# Camera_IR.net
KiCad netlist of a schematic drawn in EasyEDA
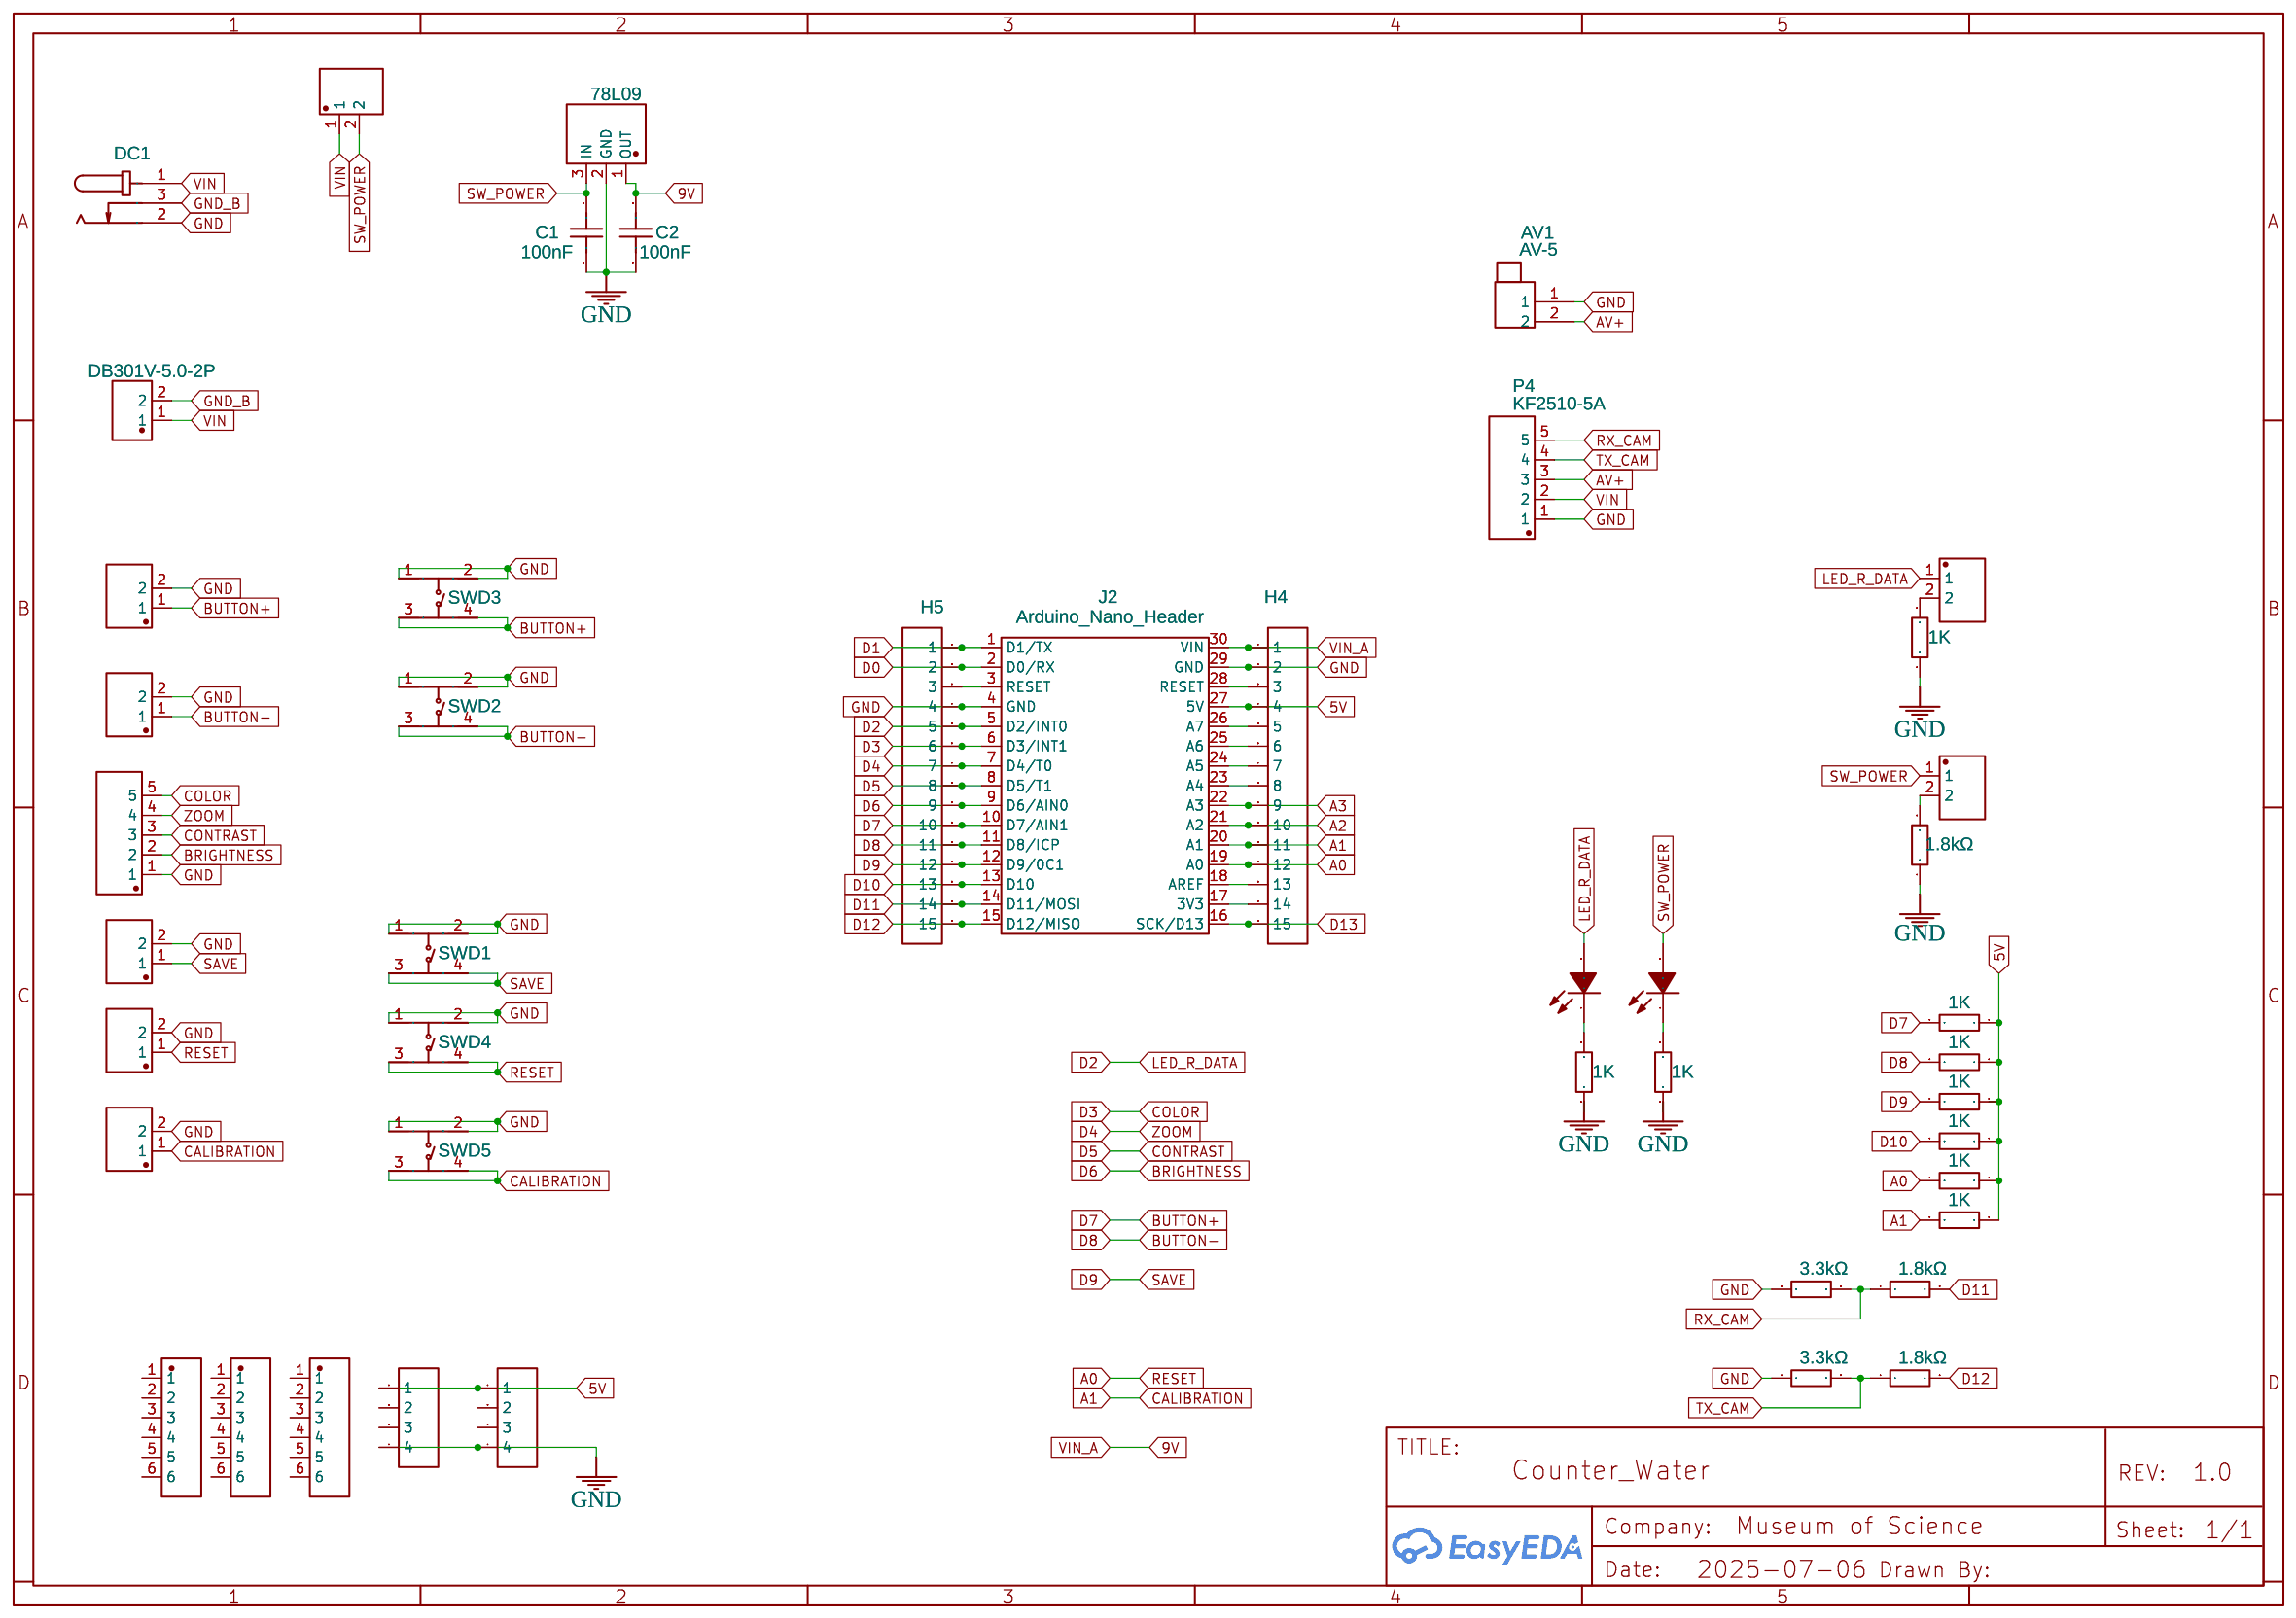
[diagram p0: schematic sheet]

(export (version "E")
  (design (tool "Eeschema 10.0.6"))
  (components
    (comp (ref "A0")
      (value "RESET")
      (fields (field (name "Manufacturer Part") "KF2510-2A") (field (name "Manufacturer") "BOOMELE"))
      (libsource (lib "") (part "KF2510-2A"))
    )
    (comp (ref "A1")
      (value "FFC")
      (fields (field (name "Manufacturer Part") "KF2510-2A") (field (name "Manufacturer") "BOOMELE"))
      (libsource (lib "") (part "KF2510-2A"))
    )
    (comp (ref "AV1")
      (value "AV-5")
      (fields (field (name "Manufacturer") "BOOMELE(博穆精密)"))
      (libsource (lib "") (part "AV-5"))
    )
    (comp (ref "C1")
      (value "100nF")
      (fields
        (field (name "Manufacturer Part") "CC0603KRX7R9BB104")
        (field (name "Manufacturer") "YAGEO(国巨)")
      )
      (libsource (lib "") (part "CC0603KRX7R9BB104"))
    )
    (comp (ref "C2")
      (value "100nF")
      (fields
        (field (name "Manufacturer Part") "CC0603KRX7R9BB104")
        (field (name "Manufacturer") "YAGEO(国巨)")
      )
      (libsource (lib "") (part "CC0603KRX7R9BB104"))
    )
    (comp (ref "D2")
      (value "LED")
      (fields (field (name "Manufacturer Part") "KF2510-2A") (field (name "Manufacturer") "BOOMELE"))
      (libsource (lib "") (part "KF2510-2A_3"))
    )
    (comp (ref "D7")
      (value "B+")
      (fields (field (name "Manufacturer Part") "KF2510-2A") (field (name "Manufacturer") "BOOMELE"))
      (libsource (lib "") (part "KF2510-2A_1"))
    )
    (comp (ref "D8")
      (value "B-")
      (fields (field (name "Manufacturer Part") "KF2510-2A") (field (name "Manufacturer") "BOOMELE"))
      (libsource (lib "") (part "KF2510-2A_1"))
    )
    (comp (ref "D9")
      (value "SAVE")
      (fields (field (name "Manufacturer Part") "KF2510-2A") (field (name "Manufacturer") "BOOMELE"))
      (libsource (lib "") (part "KF2510-2A_1"))
    )
    (comp (ref "DC1")
      (value "DC")
      (fields (field (name "Manufacturer Part") "DC005-2.0MM") (field (name "Manufacturer") "SOFNG"))
      (libsource (lib "") (part "DC005-2.0MM"))
    )
    (comp (ref "ERL1")
      (value "1K")
      (fields (field (name "Manufacturer Part") "0603WAF1001T5E") (field (name "Manufacturer") "UniOhm"))
      (libsource (lib "") (part "0603WAF1001T5E_1"))
    )
    (comp (ref "ERL2")
      (value "1K")
      (fields (field (name "Manufacturer Part") "0603WAF1001T5E") (field (name "Manufacturer") "UniOhm"))
      (libsource (lib "") (part "0603WAF1001T5E"))
    )
    (comp (ref "ERL3")
      (value "1K")
      (fields (field (name "Manufacturer Part") "0603WAF1001T5E") (field (name "Manufacturer") "UniOhm"))
      (libsource (lib "") (part "0603WAF1001T5E"))
    )
    (comp (ref "ERL4")
      (value "1K")
      (fields (field (name "Manufacturer Part") "0603WAF1001T5E") (field (name "Manufacturer") "UniOhm"))
      (libsource (lib "") (part "0603WAF1001T5E_1"))
    )
    (comp (ref "ERL5")
      (value "1K")
      (fields (field (name "Manufacturer Part") "0603WAF1001T5E") (field (name "Manufacturer") "UniOhm"))
      (libsource (lib "") (part "0603WAF1001T5E_1"))
    )
    (comp (ref "ERL6")
      (value "1K")
      (fields (field (name "Manufacturer Part") "0603WAF1001T5E") (field (name "Manufacturer") "UniOhm"))
      (libsource (lib "") (part "0603WAF1001T5E"))
    )
    (comp (ref "ERL9")
      (value "1K")
      (fields (field (name "Manufacturer Part") "0603WAF1001T5E") (field (name "Manufacturer") "UniOhm"))
      (libsource (lib "") (part "0603WAF1001T5E"))
    )
    (comp (ref "ERL11")
      (value "1K")
      (fields (field (name "Manufacturer Part") "0603WAF1001T5E") (field (name "Manufacturer") "UniOhm"))
      (libsource (lib "") (part "0603WAF1001T5E"))
    )
    (comp (ref "ERL12")
      (value "1K")
      (fields (field (name "Manufacturer Part") "0603WAF1001T5E") (field (name "Manufacturer") "UniOhm"))
      (libsource (lib "") (part "0603WAF1001T5E"))
    )
    (comp (ref "H4") (value "HDR-F-2.54_1x15") (libsource (lib "") (part "HDR-F-2.54_1x15_1")))
    (comp (ref "H5") (value "HDR-F-2.54_1x15") (libsource (lib "") (part "HDR-F-2.54_1x15")))
    (comp (ref "J2") (value "Arduino_Nano_Header") (libsource (lib "") (part "Arduino_Nano_Header")))
    (comp (ref "J6") (value "HDR-M-2.54_1x4") (libsource (lib "") (part "HDR-M-2.54_1x4")))
    (comp (ref "J7") (value "HDR-M-2.54_1x4") (libsource (lib "") (part "HDR-M-2.54_1x4")))
    (comp (ref "LED4")
      (value "KT-0603R")
      (fields (field (name "Manufacturer") "KENTO"))
      (libsource (lib "") (part "KT-0603R"))
    )
    (comp (ref "LED5")
      (value "KT-0603R")
      (fields (field (name "Manufacturer") "KENTO"))
      (libsource (lib "") (part "KT-0603R"))
    )
    (comp (ref "LED_P")
      (value "LED_POWER")
      (fields (field (name "Manufacturer Part") "KF2510-2A") (field (name "Manufacturer") "BOOMELE"))
      (libsource (lib "") (part "KF2510-2A_2"))
    )
    (comp (ref "P1")
      (value "KF2510-5A")
      (fields (field (name "Manufacturer Part") "2510-5A") (field (name "Manufacturer") "BOOMELE(博穆精密)"))
      (libsource (lib "") (part "KF2510-5A"))
    )
    (comp (ref "P2")
      (value "H6")
      (fields (field (name "Manufacturer Part") "2.54-1*6P母") (field (name "Manufacturer") "BOOMELE(博穆精密)"))
      (libsource (lib "") (part "Header-Female-2.54_1x6"))
    )
    (comp (ref "P3")
      (value "H6")
      (fields (field (name "Manufacturer Part") "2.54-1*6P母") (field (name "Manufacturer") "BOOMELE(博穆精密)"))
      (libsource (lib "") (part "Header-Female-2.54_1x6"))
    )
    (comp (ref "P4")
      (value "KF2510-5A")
      (fields (field (name "Manufacturer Part") "2510-5A") (field (name "Manufacturer") "BOOMELE(博穆精密)"))
      (libsource (lib "") (part "KF2510-5A"))
    )
    (comp (ref "P5")
      (value "H6")
      (fields (field (name "Manufacturer Part") "2.54-1*6P母") (field (name "Manufacturer") "BOOMELE(博穆精密)"))
      (libsource (lib "") (part "Header-Female-2.54_1x6"))
    )
    (comp (ref "R1")
      (value "1.8kΩ")
      (fields
        (field (name "Manufacturer Part") "0603WAF1801T5E")
        (field (name "Manufacturer") "UNI-ROYAL(厚声)")
      )
      (libsource (lib "") (part "0603WAF1801T5E_1"))
    )
    (comp (ref "R2")
      (value "1.8kΩ")
      (fields
        (field (name "Manufacturer Part") "0603WAF1801T5E")
        (field (name "Manufacturer") "UNI-ROYAL(厚声)")
      )
      (libsource (lib "") (part "0603WAF1801T5E_1"))
    )
    (comp (ref "R3")
      (value "3.3kΩ")
      (fields
        (field (name "Manufacturer Part") "0402WGF3301TCE")
        (field (name "Manufacturer") "UNI-ROYAL(厚声)")
      )
      (libsource (lib "") (part "0402WGF3301TCE"))
    )
    (comp (ref "R4")
      (value "3.3kΩ")
      (fields
        (field (name "Manufacturer Part") "0402WGF3301TCE")
        (field (name "Manufacturer") "UNI-ROYAL(厚声)")
      )
      (libsource (lib "") (part "0402WGF3301TCE"))
    )
    (comp (ref "R5")
      (value "1.8kΩ")
      (fields
        (field (name "Manufacturer Part") "0603WAF1801T5E")
        (field (name "Manufacturer") "UNI-ROYAL(厚声)")
      )
      (libsource (lib "") (part "0603WAF1801T5E"))
    )
    (comp (ref "SWD1")
      (value "TC-6610-7-160G")
      (fields (field (name "Manufacturer") "HCTL(华灿天禄)"))
      (libsource (lib "") (part "TC-6610-7-160G"))
    )
    (comp (ref "SWD2")
      (value "TC-6610-7-160G")
      (fields (field (name "Manufacturer") "HCTL(华灿天禄)"))
      (libsource (lib "") (part "TC-6610-7-160G"))
    )
    (comp (ref "SWD3")
      (value "TC-6610-7-160G")
      (fields (field (name "Manufacturer") "HCTL(华灿天禄)"))
      (libsource (lib "") (part "TC-6610-7-160G"))
    )
    (comp (ref "SWD4")
      (value "TC-6610-7-160G")
      (fields (field (name "Manufacturer") "HCTL(华灿天禄)"))
      (libsource (lib "") (part "TC-6610-7-160G"))
    )
    (comp (ref "SWD5")
      (value "TC-6610-7-160G")
      (fields (field (name "Manufacturer") "HCTL(华灿天禄)"))
      (libsource (lib "") (part "TC-6610-7-160G"))
    )
    (comp (ref "SW_P")
      (value "SW_P")
      (fields (field (name "Manufacturer Part") "KF2510-2A") (field (name "Manufacturer") "BOOMELE"))
      (libsource (lib "") (part "KF2510-2A_4"))
    )
    (comp (ref "U1")
      (value "78L09")
      (fields (field (name "Manufacturer") "CBI(创基)"))
      (libsource (lib "") (part "78L09U 78L09"))
    )
    (comp (ref "U3")
      (value "DB301V-5.0-2P")
      (fields
        (field (name "Manufacturer Part") "DB301V-5.0-2P-BU-S")
        (field (name "Manufacturer") "DORABO(地博电气)")
      )
      (libsource (lib "") (part "DB301V-5.0-2P"))
    )
  )
  (nets
    (net (code "1") (name "5V") (class "Default")
      (node (ref "ERL11") (pin "1") (pinfunction "1_1") (pintype "input"))
      (node (ref "ERL12") (pin "1") (pinfunction "1_1") (pintype "input"))
      (node (ref "ERL2") (pin "1") (pinfunction "1_1") (pintype "input"))
      (node (ref "ERL3") (pin "1") (pinfunction "1_1") (pintype "input"))
      (node (ref "ERL6") (pin "1") (pinfunction "1_1") (pintype "input"))
      (node (ref "ERL9") (pin "1") (pinfunction "1_1") (pintype "input"))
      (node (ref "H4") (pin "4") (pinfunction "4_4") (pintype "unspecified"))
      (node (ref "J2") (pin "27") (pinfunction "5V_27") (pintype "unspecified"))
      (node (ref "J6") (pin "1") (pinfunction "1_1") (pintype "unspecified"))
      (node (ref "J7") (pin "1") (pinfunction "1_1") (pintype "unspecified"))
    )
    (net (code "2") (name "9V") (class "Default")
      (node (ref "C2") (pin "2") (pinfunction "2_2") (pintype "unspecified"))
      (node (ref "H4") (pin "1") (pinfunction "1_1") (pintype "unspecified"))
      (node (ref "J2") (pin "30") (pinfunction "VIN_30") (pintype "unspecified"))
      (node (ref "U1") (pin "1") (pinfunction "OUT_1") (pintype "unspecified"))
    )
    (net (code "3") (name "A0") (class "Default")
      (node (ref "A0") (pin "1") (pinfunction "1_1") (pintype "unspecified"))
      (node (ref "ERL2") (pin "2") (pinfunction "2_2") (pintype "input"))
      (node (ref "H4") (pin "12") (pinfunction "12_12") (pintype "unspecified"))
      (node (ref "J2") (pin "19") (pinfunction "A0_19") (pintype "unspecified"))
      (node (ref "SWD4") (pin "3") (pinfunction "3_3") (pintype "unspecified"))
      (node (ref "SWD4") (pin "4") (pinfunction "4_4") (pintype "unspecified"))
    )
    (net (code "4") (name "A1") (class "Default")
      (node (ref "A1") (pin "1") (pinfunction "1_1") (pintype "unspecified"))
      (node (ref "ERL3") (pin "2") (pinfunction "2_2") (pintype "input"))
      (node (ref "H4") (pin "11") (pinfunction "11_11") (pintype "unspecified"))
      (node (ref "J2") (pin "20") (pinfunction "A1_20") (pintype "unspecified"))
      (node (ref "SWD5") (pin "3") (pinfunction "3_3") (pintype "unspecified"))
      (node (ref "SWD5") (pin "4") (pinfunction "4_4") (pintype "unspecified"))
    )
    (net (code "5") (name "A2") (class "Default")
      (node (ref "H4") (pin "10") (pinfunction "10_10") (pintype "unspecified"))
      (node (ref "J2") (pin "21") (pinfunction "A2_21") (pintype "unspecified"))
    )
    (net (code "6") (name "A3") (class "Default")
      (node (ref "H4") (pin "9") (pinfunction "9_9") (pintype "unspecified"))
      (node (ref "J2") (pin "22") (pinfunction "A3_22") (pintype "unspecified"))
    )
    (net (code "7") (name "AV+") (class "Default")
      (node (ref "AV1") (pin "2") (pinfunction "2_2") (pintype "unspecified"))
      (node (ref "P4") (pin "3") (pinfunction "3_3") (pintype "unspecified"))
    )
    (net (code "8") (name "BRIGHTNESS") (class "Default")
      (node (ref "H5") (pin "9") (pinfunction "9_9") (pintype "unspecified"))
      (node (ref "J2") (pin "9") (pinfunction "D6/AIN0_9") (pintype "unspecified"))
      (node (ref "P1") (pin "2") (pinfunction "2_2") (pintype "unspecified"))
    )
    (net (code "9") (name "BUTTON+") (class "Default")
      (node (ref "D7") (pin "1") (pinfunction "1_1") (pintype "unspecified"))
      (node (ref "ERL6") (pin "2") (pinfunction "2_2") (pintype "input"))
      (node (ref "H5") (pin "10") (pinfunction "10_10") (pintype "unspecified"))
      (node (ref "J2") (pin "10") (pinfunction "D7/AIN1_10") (pintype "unspecified"))
      (node (ref "SWD3") (pin "3") (pinfunction "3_3") (pintype "unspecified"))
      (node (ref "SWD3") (pin "4") (pinfunction "4_4") (pintype "unspecified"))
    )
    (net (code "10") (name "BUTTON-") (class "Default")
      (node (ref "D8") (pin "1") (pinfunction "1_1") (pintype "unspecified"))
      (node (ref "ERL11") (pin "2") (pinfunction "2_2") (pintype "input"))
      (node (ref "H5") (pin "11") (pinfunction "11_11") (pintype "unspecified"))
      (node (ref "J2") (pin "11") (pinfunction "D8/ICP_11") (pintype "unspecified"))
      (node (ref "SWD2") (pin "3") (pinfunction "3_3") (pintype "unspecified"))
      (node (ref "SWD2") (pin "4") (pinfunction "4_4") (pintype "unspecified"))
    )
    (net (code "11") (name "COLOR") (class "Default")
      (node (ref "H5") (pin "6") (pinfunction "6_6") (pintype "unspecified"))
      (node (ref "J2") (pin "6") (pinfunction "D3/INT1_6") (pintype "unspecified"))
      (node (ref "P1") (pin "5") (pinfunction "5_5") (pintype "unspecified"))
    )
    (net (code "12") (name "CONTRAST") (class "Default")
      (node (ref "H5") (pin "8") (pinfunction "8_8") (pintype "unspecified"))
      (node (ref "J2") (pin "8") (pinfunction "D5/T1_8") (pintype "unspecified"))
      (node (ref "P1") (pin "3") (pinfunction "3_3") (pintype "unspecified"))
    )
    (net (code "13") (name "D0") (class "Default")
      (node (ref "H5") (pin "2") (pinfunction "2_2") (pintype "unspecified"))
      (node (ref "J2") (pin "2") (pinfunction "D0/RX_2") (pintype "unspecified"))
    )
    (net (code "14") (name "D1") (class "Default")
      (node (ref "H5") (pin "1") (pinfunction "1_1") (pintype "unspecified"))
      (node (ref "J2") (pin "1") (pinfunction "D1/TX_1") (pintype "unspecified"))
    )
    (net (code "15") (name "D2") (class "Default")
      (node (ref "D2") (pin "1") (pinfunction "1_1") (pintype "unspecified"))
      (node (ref "H5") (pin "5") (pinfunction "5_5") (pintype "unspecified"))
      (node (ref "J2") (pin "5") (pinfunction "D2/INT0_5") (pintype "unspecified"))
      (node (ref "LED5") (pin "2") (pinfunction "A_2") (pintype "unspecified"))
    )
    (net (code "16") (name "D4") (class "Default")
      (node (ref "H5") (pin "7") (pinfunction "7_7") (pintype "unspecified"))
      (node (ref "J2") (pin "7") (pinfunction "D4/T0_7") (pintype "unspecified"))
      (node (ref "P1") (pin "4") (pinfunction "4_4") (pintype "unspecified"))
    )
    (net (code "17") (name "D9") (class "Default")
      (node (ref "D9") (pin "1") (pinfunction "1_1") (pintype "unspecified"))
      (node (ref "ERL9") (pin "2") (pinfunction "2_2") (pintype "input"))
      (node (ref "H5") (pin "12") (pinfunction "12_12") (pintype "unspecified"))
      (node (ref "J2") (pin "12") (pinfunction "D9/0C1_12") (pintype "unspecified"))
      (node (ref "SWD1") (pin "3") (pinfunction "3_3") (pintype "unspecified"))
      (node (ref "SWD1") (pin "4") (pinfunction "4_4") (pintype "unspecified"))
    )
    (net (code "18") (name "D10") (class "Default")
      (node (ref "ERL12") (pin "2") (pinfunction "2_2") (pintype "input"))
      (node (ref "H5") (pin "13") (pinfunction "13_13") (pintype "unspecified"))
      (node (ref "J2") (pin "13") (pinfunction "D10_13") (pintype "unspecified"))
    )
    (net (code "19") (name "D11") (class "Default")
      (node (ref "H5") (pin "14") (pinfunction "14_14") (pintype "unspecified"))
      (node (ref "J2") (pin "14") (pinfunction "D11/MOSI_14") (pintype "unspecified"))
      (node (ref "R1") (pin "2") (pinfunction "2_2") (pintype "input"))
    )
    (net (code "20") (name "D12") (class "Default")
      (node (ref "H5") (pin "15") (pinfunction "15_15") (pintype "unspecified"))
      (node (ref "J2") (pin "15") (pinfunction "D12/MISO_15") (pintype "unspecified"))
      (node (ref "R2") (pin "2") (pinfunction "2_2") (pintype "input"))
    )
    (net (code "21") (name "D13") (class "Default")
      (node (ref "H4") (pin "15") (pinfunction "15_15") (pintype "unspecified"))
      (node (ref "J2") (pin "16") (pinfunction "SCK/D13_16") (pintype "unspecified"))
    )
    (net (code "22") (name "GND") (class "Default")
      (node (ref "A0") (pin "2") (pinfunction "2_2") (pintype "unspecified"))
      (node (ref "A1") (pin "2") (pinfunction "2_2") (pintype "unspecified"))
      (node (ref "AV1") (pin "1") (pinfunction "1_1") (pintype "unspecified"))
      (node (ref "C1") (pin "1") (pinfunction "1_1") (pintype "unspecified"))
      (node (ref "C2") (pin "1") (pinfunction "1_1") (pintype "unspecified"))
      (node (ref "D7") (pin "2") (pinfunction "2_2") (pintype "unspecified"))
      (node (ref "D8") (pin "2") (pinfunction "2_2") (pintype "unspecified"))
      (node (ref "D9") (pin "2") (pinfunction "2_2") (pintype "unspecified"))
      (node (ref "DC1") (pin "2") (pinfunction "2_2") (pintype "unspecified"))
      (node (ref "ERL1") (pin "1") (pinfunction "1_1") (pintype "input"))
      (node (ref "ERL4") (pin "1") (pinfunction "1_1") (pintype "input"))
      (node (ref "ERL5") (pin "1") (pinfunction "1_1") (pintype "input"))
      (node (ref "H4") (pin "2") (pinfunction "2_2") (pintype "unspecified"))
      (node (ref "H5") (pin "4") (pinfunction "4_4") (pintype "unspecified"))
      (node (ref "J2") (pin "29") (pinfunction "GND_29") (pintype "unspecified"))
      (node (ref "J2") (pin "4") (pinfunction "GND_4") (pintype "unspecified"))
      (node (ref "J6") (pin "4") (pinfunction "4_4") (pintype "unspecified"))
      (node (ref "J7") (pin "4") (pinfunction "4_4") (pintype "unspecified"))
      (node (ref "P1") (pin "1") (pinfunction "1_1") (pintype "unspecified"))
      (node (ref "P4") (pin "1") (pinfunction "1_1") (pintype "unspecified"))
      (node (ref "R3") (pin "1") (pinfunction "1_1") (pintype "input"))
      (node (ref "R4") (pin "1") (pinfunction "1_1") (pintype "input"))
      (node (ref "R5") (pin "1") (pinfunction "1_1") (pintype "input"))
      (node (ref "SWD1") (pin "1") (pinfunction "1_1") (pintype "unspecified"))
      (node (ref "SWD1") (pin "2") (pinfunction "2_2") (pintype "unspecified"))
      (node (ref "SWD2") (pin "1") (pinfunction "1_1") (pintype "unspecified"))
      (node (ref "SWD2") (pin "2") (pinfunction "2_2") (pintype "unspecified"))
      (node (ref "SWD3") (pin "1") (pinfunction "1_1") (pintype "unspecified"))
      (node (ref "SWD3") (pin "2") (pinfunction "2_2") (pintype "unspecified"))
      (node (ref "SWD4") (pin "1") (pinfunction "1_1") (pintype "unspecified"))
      (node (ref "SWD4") (pin "2") (pinfunction "2_2") (pintype "unspecified"))
      (node (ref "SWD5") (pin "1") (pinfunction "1_1") (pintype "unspecified"))
      (node (ref "SWD5") (pin "2") (pinfunction "2_2") (pintype "unspecified"))
      (node (ref "U1") (pin "2") (pinfunction "GND_2") (pintype "unspecified"))
    )
    (net (code "23") (name "GND_B") (class "Default")
      (node (ref "DC1") (pin "3") (pinfunction "3_3") (pintype "unspecified"))
      (node (ref "U3") (pin "2") (pinfunction "2_2") (pintype "unspecified"))
    )
    (net (code "24") (name "Net-(D2-Pad2)") (class "Default")
      (node (ref "D2") (pin "2") (pinfunction "2_2") (pintype "unspecified"))
      (node (ref "ERL5") (pin "2") (pinfunction "2_2") (pintype "input"))
    )
    (net (code "25") (name "Net-(H4-Pad3)") (class "Default")
      (node (ref "H4") (pin "3") (pinfunction "3_3") (pintype "unspecified"))
      (node (ref "J2") (pin "28") (pinfunction "RESET_28") (pintype "unspecified"))
    )
    (net (code "26") (name "Net-(H5-Pad3)") (class "Default")
      (node (ref "H5") (pin "3") (pinfunction "3_3") (pintype "unspecified"))
      (node (ref "J2") (pin "3") (pinfunction "RESET_3") (pintype "unspecified"))
    )
    (net (code "27") (name "Net-(J2-3V3)") (class "Default")
      (node (ref "H4") (pin "14") (pinfunction "14_14") (pintype "unspecified"))
      (node (ref "J2") (pin "17") (pinfunction "3V3_17") (pintype "unspecified"))
    )
    (net (code "28") (name "Net-(J2-A4)") (class "Default")
      (node (ref "H4") (pin "8") (pinfunction "8_8") (pintype "unspecified"))
      (node (ref "J2") (pin "23") (pinfunction "A4_23") (pintype "unspecified"))
    )
    (net (code "29") (name "Net-(J2-A5)") (class "Default")
      (node (ref "H4") (pin "7") (pinfunction "7_7") (pintype "unspecified"))
      (node (ref "J2") (pin "24") (pinfunction "A5_24") (pintype "unspecified"))
    )
    (net (code "30") (name "Net-(J2-A6)") (class "Default")
      (node (ref "H4") (pin "6") (pinfunction "6_6") (pintype "unspecified"))
      (node (ref "J2") (pin "25") (pinfunction "A6_25") (pintype "unspecified"))
    )
    (net (code "31") (name "Net-(J2-A7)") (class "Default")
      (node (ref "H4") (pin "5") (pinfunction "5_5") (pintype "unspecified"))
      (node (ref "J2") (pin "26") (pinfunction "A7_26") (pintype "unspecified"))
    )
    (net (code "32") (name "Net-(J2-AREF)") (class "Default")
      (node (ref "H4") (pin "13") (pinfunction "13_13") (pintype "unspecified"))
      (node (ref "J2") (pin "18") (pinfunction "AREF_18") (pintype "unspecified"))
    )
    (net (code "33") (name "Net-(LED4-K)") (class "Default")
      (node (ref "ERL4") (pin "2") (pinfunction "2_2") (pintype "input"))
      (node (ref "LED4") (pin "1") (pinfunction "K_1") (pintype "unspecified"))
    )
    (net (code "34") (name "Net-(LED5-K)") (class "Default")
      (node (ref "ERL1") (pin "2") (pinfunction "2_2") (pintype "input"))
      (node (ref "LED5") (pin "1") (pinfunction "K_1") (pintype "unspecified"))
    )
    (net (code "35") (name "Net-(LED_P-Pad2)") (class "Default")
      (node (ref "LED_P") (pin "2") (pinfunction "2_2") (pintype "unspecified"))
      (node (ref "R5") (pin "2") (pinfunction "2_2") (pintype "input"))
    )
    (net (code "36") (name "RX_CAM") (class "Default")
      (node (ref "P4") (pin "5") (pinfunction "5_5") (pintype "unspecified"))
      (node (ref "R1") (pin "1") (pinfunction "1_1") (pintype "input"))
      (node (ref "R3") (pin "2") (pinfunction "2_2") (pintype "input"))
    )
    (net (code "37") (name "SW_POWER") (class "Default")
      (node (ref "C1") (pin "2") (pinfunction "2_2") (pintype "unspecified"))
      (node (ref "LED4") (pin "2") (pinfunction "A_2") (pintype "unspecified"))
      (node (ref "LED_P") (pin "1") (pinfunction "1_1") (pintype "unspecified"))
      (node (ref "SW_P") (pin "2") (pinfunction "2_2") (pintype "unspecified"))
      (node (ref "U1") (pin "3") (pinfunction "IN_3") (pintype "unspecified"))
    )
    (net (code "38") (name "TX_CAM") (class "Default")
      (node (ref "P4") (pin "4") (pinfunction "4_4") (pintype "unspecified"))
      (node (ref "R2") (pin "1") (pinfunction "1_1") (pintype "input"))
      (node (ref "R4") (pin "2") (pinfunction "2_2") (pintype "input"))
    )
    (net (code "39") (name "VIN") (class "Default")
      (node (ref "DC1") (pin "1") (pinfunction "1_1") (pintype "unspecified"))
      (node (ref "P4") (pin "2") (pinfunction "2_2") (pintype "unspecified"))
      (node (ref "SW_P") (pin "1") (pinfunction "1_1") (pintype "unspecified"))
      (node (ref "U3") (pin "1") (pinfunction "1_1") (pintype "unspecified"))
    )
    (net (code "40") (name "unconnected-(J6-Pad2)") (class "Default")
      (node (ref "J6") (pin "2") (pinfunction "2_2") (pintype "unspecified"))
    )
    (net (code "41") (name "unconnected-(J6-Pad3)") (class "Default")
      (node (ref "J6") (pin "3") (pinfunction "3_3") (pintype "unspecified"))
    )
    (net (code "42") (name "unconnected-(J7-Pad2)") (class "Default")
      (node (ref "J7") (pin "2") (pinfunction "2_2") (pintype "unspecified"))
    )
    (net (code "43") (name "unconnected-(J7-Pad3)") (class "Default")
      (node (ref "J7") (pin "3") (pinfunction "3_3") (pintype "unspecified"))
    )
    (net (code "44") (name "unconnected-(P2-Pad1)") (class "Default")
      (node (ref "P2") (pin "1") (pinfunction "1_1") (pintype "unspecified"))
    )
    (net (code "45") (name "unconnected-(P2-Pad2)") (class "Default")
      (node (ref "P2") (pin "2") (pinfunction "2_2") (pintype "unspecified"))
    )
    (net (code "46") (name "unconnected-(P2-Pad3)") (class "Default")
      (node (ref "P2") (pin "3") (pinfunction "3_3") (pintype "unspecified"))
    )
    (net (code "47") (name "unconnected-(P2-Pad4)") (class "Default")
      (node (ref "P2") (pin "4") (pinfunction "4_4") (pintype "unspecified"))
    )
    (net (code "48") (name "unconnected-(P2-Pad5)") (class "Default")
      (node (ref "P2") (pin "5") (pinfunction "5_5") (pintype "unspecified"))
    )
    (net (code "49") (name "unconnected-(P2-Pad6)") (class "Default")
      (node (ref "P2") (pin "6") (pinfunction "6_6") (pintype "unspecified"))
    )
    (net (code "50") (name "unconnected-(P3-Pad1)") (class "Default")
      (node (ref "P3") (pin "1") (pinfunction "1_1") (pintype "unspecified"))
    )
    (net (code "51") (name "unconnected-(P3-Pad2)") (class "Default")
      (node (ref "P3") (pin "2") (pinfunction "2_2") (pintype "unspecified"))
    )
    (net (code "52") (name "unconnected-(P3-Pad3)") (class "Default")
      (node (ref "P3") (pin "3") (pinfunction "3_3") (pintype "unspecified"))
    )
    (net (code "53") (name "unconnected-(P3-Pad4)") (class "Default")
      (node (ref "P3") (pin "4") (pinfunction "4_4") (pintype "unspecified"))
    )
    (net (code "54") (name "unconnected-(P3-Pad5)") (class "Default")
      (node (ref "P3") (pin "5") (pinfunction "5_5") (pintype "unspecified"))
    )
    (net (code "55") (name "unconnected-(P3-Pad6)") (class "Default")
      (node (ref "P3") (pin "6") (pinfunction "6_6") (pintype "unspecified"))
    )
    (net (code "56") (name "unconnected-(P5-Pad1)") (class "Default")
      (node (ref "P5") (pin "1") (pinfunction "1_1") (pintype "unspecified"))
    )
    (net (code "57") (name "unconnected-(P5-Pad2)") (class "Default")
      (node (ref "P5") (pin "2") (pinfunction "2_2") (pintype "unspecified"))
    )
    (net (code "58") (name "unconnected-(P5-Pad3)") (class "Default")
      (node (ref "P5") (pin "3") (pinfunction "3_3") (pintype "unspecified"))
    )
    (net (code "59") (name "unconnected-(P5-Pad4)") (class "Default")
      (node (ref "P5") (pin "4") (pinfunction "4_4") (pintype "unspecified"))
    )
    (net (code "60") (name "unconnected-(P5-Pad5)") (class "Default")
      (node (ref "P5") (pin "5") (pinfunction "5_5") (pintype "unspecified"))
    )
    (net (code "61") (name "unconnected-(P5-Pad6)") (class "Default")
      (node (ref "P5") (pin "6") (pinfunction "6_6") (pintype "unspecified"))
    )
  )
)
